# RobomasSwerve.net
KiCad netlist of a schematic drawn in EAGLE
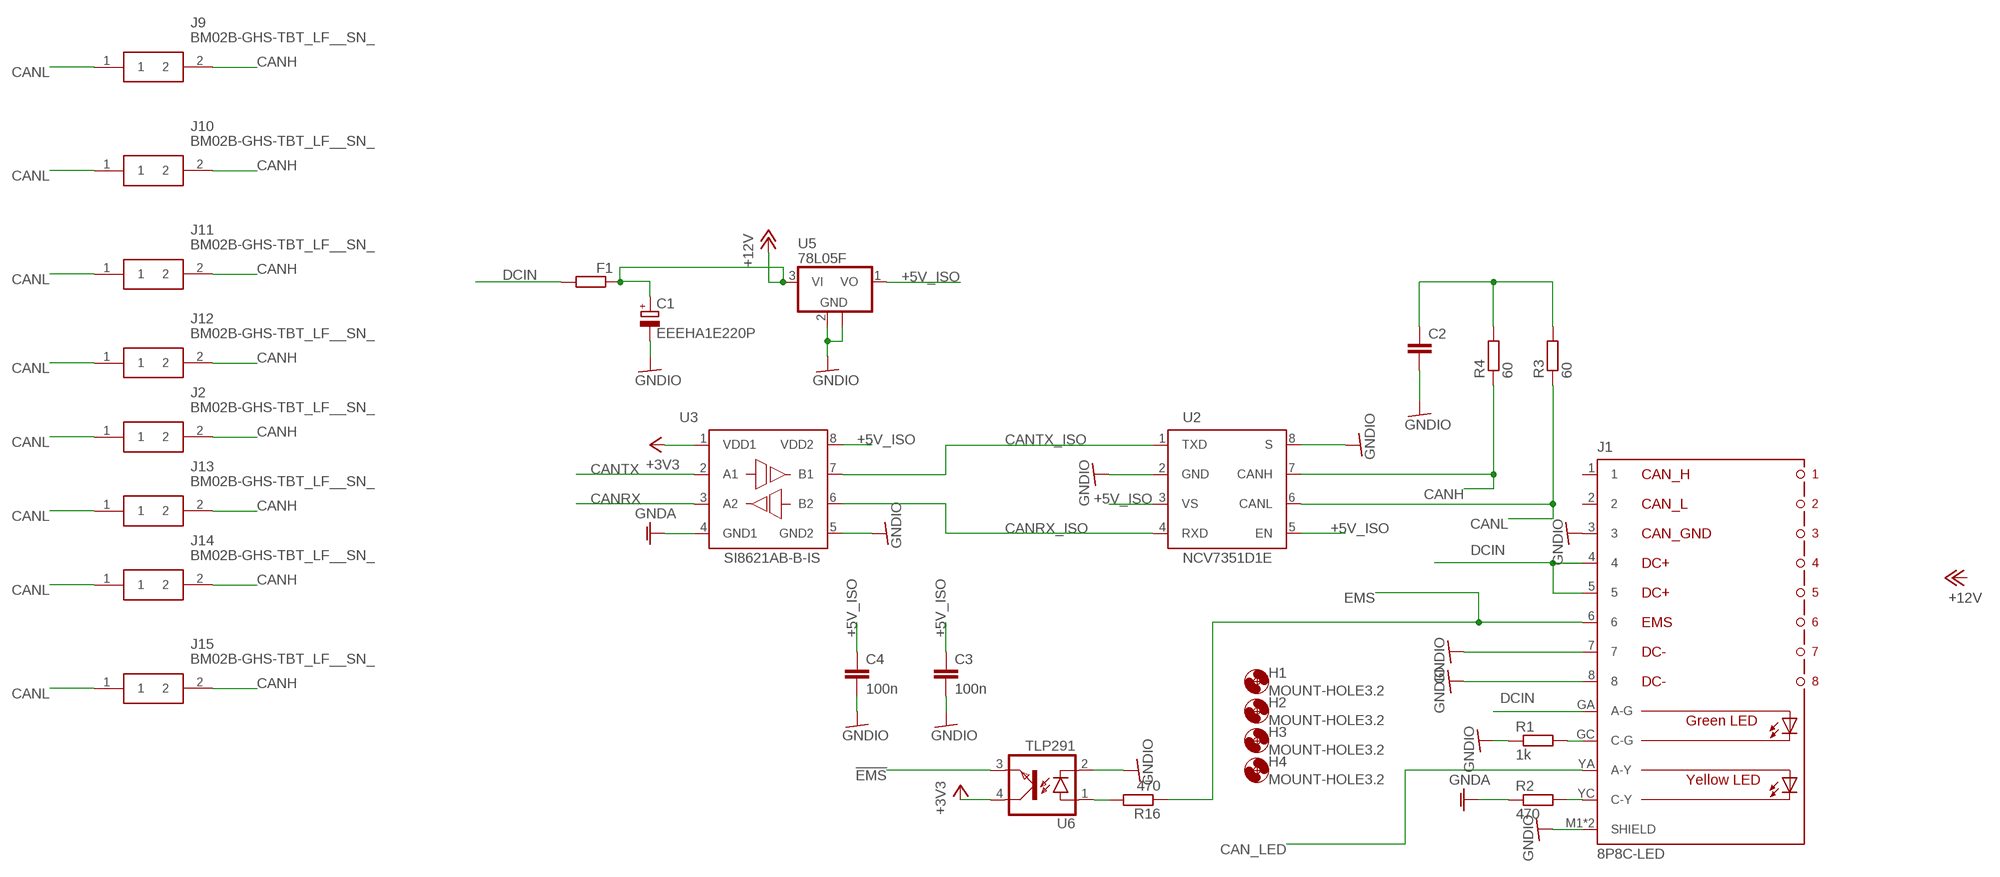
[diagram p0: schematic, sheet 1]
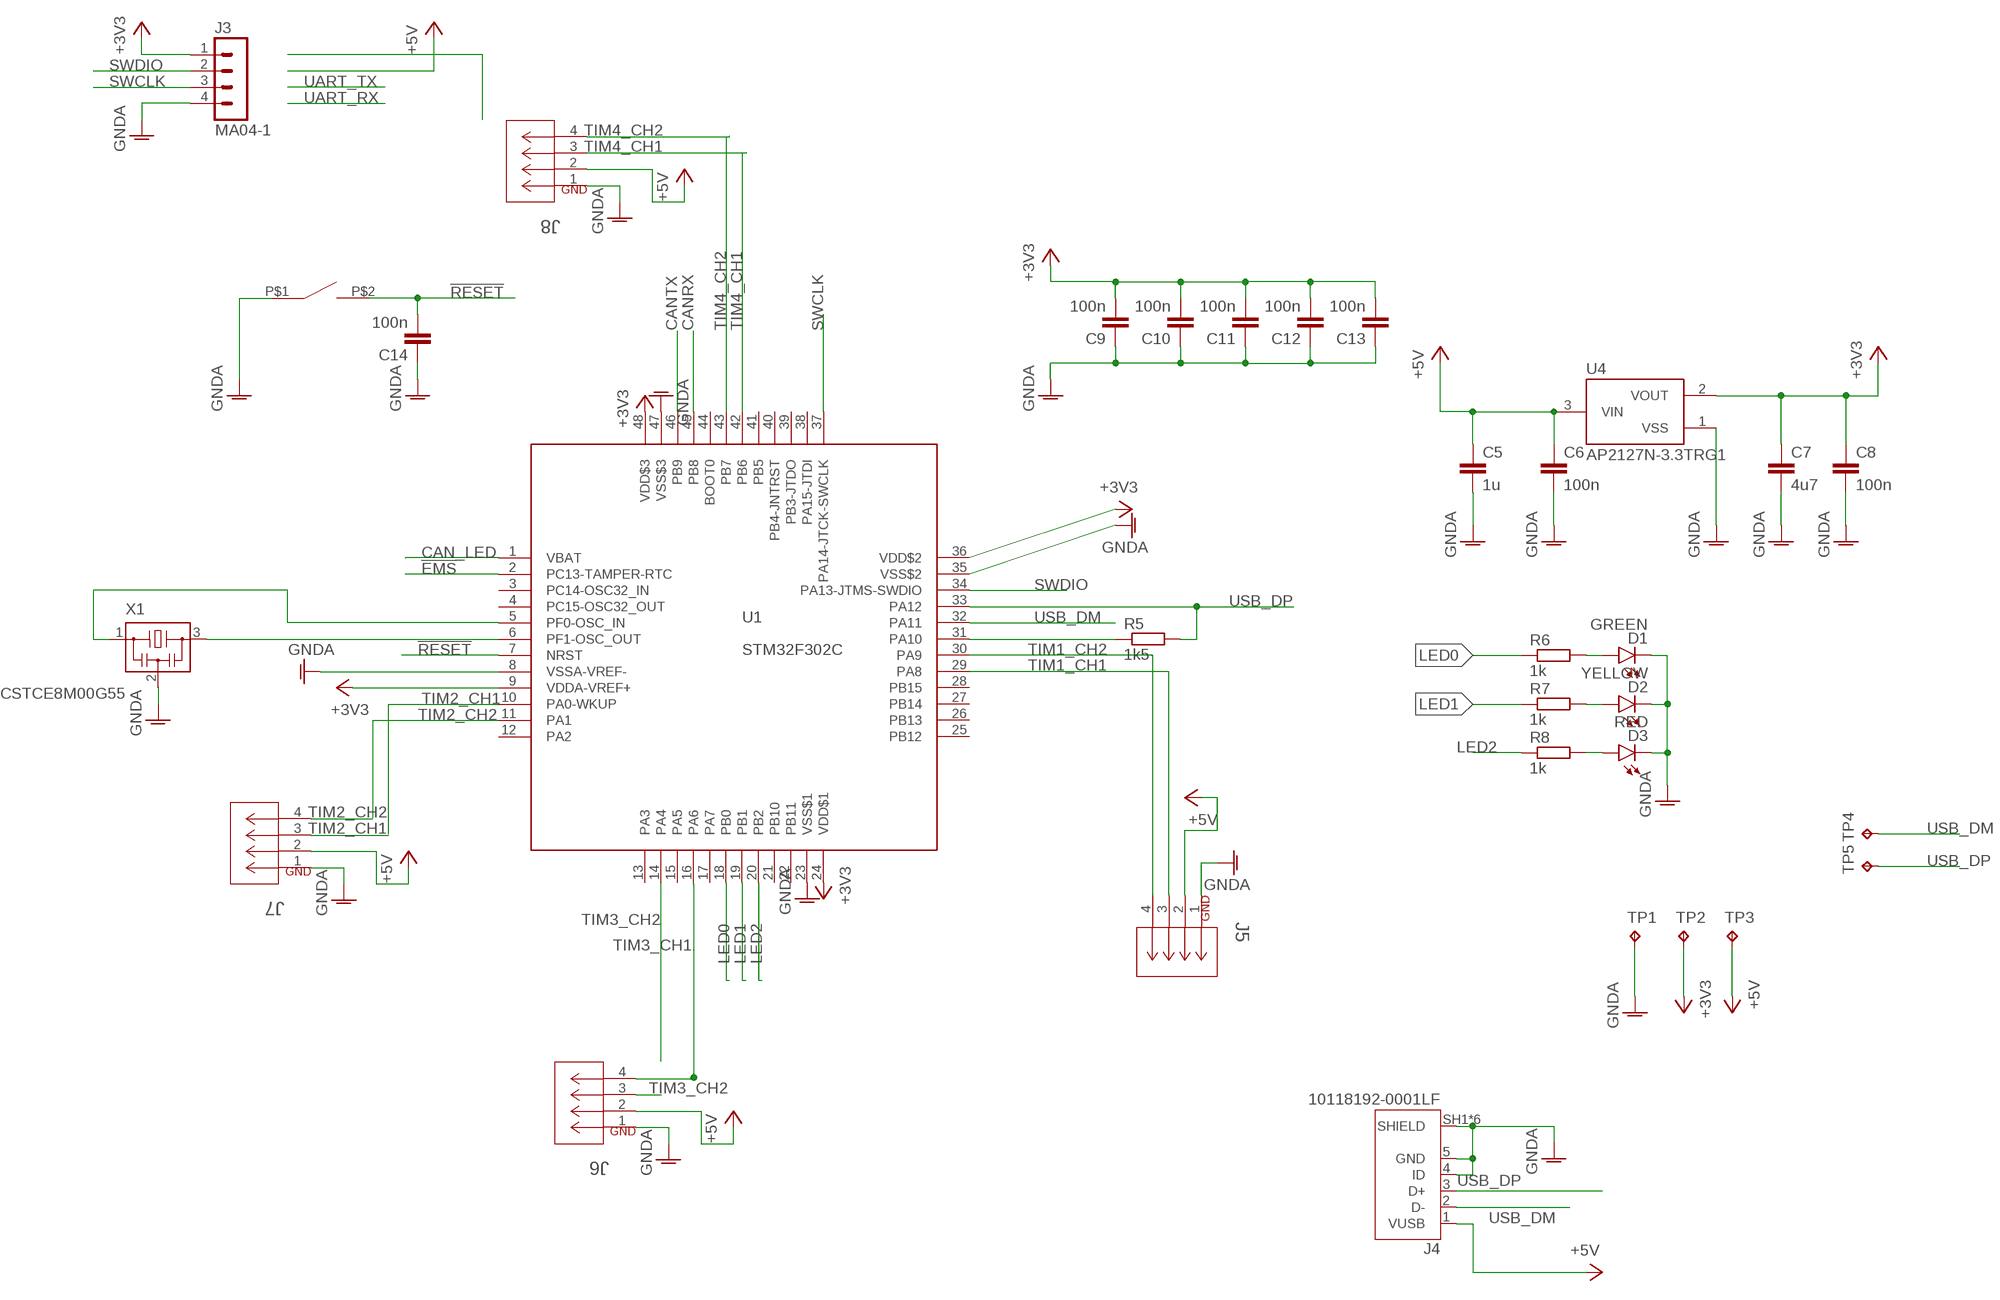
[diagram p1: schematic, sheet 2]

(export (version "E")
  (design (tool "Eeschema 10.0.6"))
  (components
    (comp (ref "C1")
      (value "EEEHA1E220P")
      (footprint "eagle-import:153CLV-0605")
      (libsource (lib "eagle-import") (part "CPOL-EU153CLV-0605"))
    )
    (comp (ref "C2")
      (value "C-EUC0603")
      (footprint "eagle-import:C0603")
      (libsource (lib "eagle-import") (part "rcl_334_C-EUC0603"))
    )
    (comp (ref "C3")
      (value "100n")
      (footprint "eagle-import:C0603")
      (libsource (lib "eagle-import") (part "rcl_334_C-EUC0603"))
    )
    (comp (ref "C4")
      (value "100n")
      (footprint "eagle-import:C0603")
      (libsource (lib "eagle-import") (part "rcl_334_C-EUC0603"))
    )
    (comp (ref "F1")
      (value "R-EU_R1206")
      (footprint "eagle-import:R1206")
      (libsource (lib "eagle-import") (part "rcl_334_R-EU_R1206"))
    )
    (comp (ref "H1")
      (value "MOUNT-HOLE3.2")
      (footprint "eagle-import:3,2")
      (libsource (lib "eagle-import") (part "MOUNT-HOLE3.2"))
    )
    (comp (ref "H2")
      (value "MOUNT-HOLE3.2")
      (footprint "eagle-import:3,2")
      (libsource (lib "eagle-import") (part "MOUNT-HOLE3.2"))
    )
    (comp (ref "H3")
      (value "MOUNT-HOLE3.2")
      (footprint "eagle-import:3,2")
      (libsource (lib "eagle-import") (part "MOUNT-HOLE3.2"))
    )
    (comp (ref "H4")
      (value "MOUNT-HOLE3.2")
      (footprint "eagle-import:3,2")
      (libsource (lib "eagle-import") (part "MOUNT-HOLE3.2"))
    )
    (comp (ref "J1")
      (value "8P8C-LED")
      (footprint "eagle-import:8P8C-LED")
      (libsource (lib "eagle-import") (part "8P8C-LED"))
    )
    (comp (ref "J2")
      (value "BM02B-GHS-TBT_LF__SN_")
      (footprint "eagle-import:BM02B-GHS-TBT_1")
      (fields (field (name "MANUFACTURER_PART_NUMBER") "BM02B-GHS-TBT(LF)(SN)"))
      (libsource (lib "eagle-import") (part "BM02B-GHS-TBT_LF__SN_"))
    )
    (comp (ref "J9")
      (value "BM02B-GHS-TBT_LF__SN_")
      (footprint "eagle-import:BM02B-GHS-TBT_1")
      (fields (field (name "MANUFACTURER_PART_NUMBER") "BM02B-GHS-TBT(LF)(SN)"))
      (libsource (lib "eagle-import") (part "BM02B-GHS-TBT_LF__SN_"))
    )
    (comp (ref "J10")
      (value "BM02B-GHS-TBT_LF__SN_")
      (footprint "eagle-import:BM02B-GHS-TBT_1")
      (fields (field (name "MANUFACTURER_PART_NUMBER") "BM02B-GHS-TBT(LF)(SN)"))
      (libsource (lib "eagle-import") (part "BM02B-GHS-TBT_LF__SN_"))
    )
    (comp (ref "J11")
      (value "BM02B-GHS-TBT_LF__SN_")
      (footprint "eagle-import:BM02B-GHS-TBT_1")
      (fields (field (name "MANUFACTURER_PART_NUMBER") "BM02B-GHS-TBT(LF)(SN)"))
      (libsource (lib "eagle-import") (part "BM02B-GHS-TBT_LF__SN_"))
    )
    (comp (ref "J12")
      (value "BM02B-GHS-TBT_LF__SN_")
      (footprint "eagle-import:BM02B-GHS-TBT_1")
      (fields (field (name "MANUFACTURER_PART_NUMBER") "BM02B-GHS-TBT(LF)(SN)"))
      (libsource (lib "eagle-import") (part "BM02B-GHS-TBT_LF__SN_"))
    )
    (comp (ref "J13")
      (value "BM02B-GHS-TBT_LF__SN_")
      (footprint "eagle-import:BM02B-GHS-TBT_1")
      (fields (field (name "MANUFACTURER_PART_NUMBER") "BM02B-GHS-TBT(LF)(SN)"))
      (libsource (lib "eagle-import") (part "BM02B-GHS-TBT_LF__SN_"))
    )
    (comp (ref "J14")
      (value "BM02B-GHS-TBT_LF__SN_")
      (footprint "eagle-import:BM02B-GHS-TBT_1")
      (fields (field (name "MANUFACTURER_PART_NUMBER") "BM02B-GHS-TBT(LF)(SN)"))
      (libsource (lib "eagle-import") (part "BM02B-GHS-TBT_LF__SN_"))
    )
    (comp (ref "J15")
      (value "BM02B-GHS-TBT_LF__SN_")
      (footprint "eagle-import:BM02B-GHS-TBT_1")
      (fields (field (name "MANUFACTURER_PART_NUMBER") "BM02B-GHS-TBT(LF)(SN)"))
      (libsource (lib "eagle-import") (part "BM02B-GHS-TBT_LF__SN_"))
    )
    (comp (ref "R1")
      (value "1k")
      (footprint "eagle-import:R0603")
      (libsource (lib "eagle-import") (part "rcl_334_R-EU_R0603"))
    )
    (comp (ref "R2")
      (value "470")
      (footprint "eagle-import:R0603")
      (libsource (lib "eagle-import") (part "rcl_334_R-EU_R0603"))
    )
    (comp (ref "R3")
      (value "60")
      (footprint "eagle-import:R0603")
      (libsource (lib "eagle-import") (part "rcl_334_R-EU_R0603"))
    )
    (comp (ref "R4")
      (value "60")
      (footprint "eagle-import:R0603")
      (libsource (lib "eagle-import") (part "rcl_334_R-EU_R0603"))
    )
    (comp (ref "R16")
      (value "470")
      (footprint "eagle-import:R0603")
      (libsource (lib "eagle-import") (part "rcl_334_R-EU_R0603"))
    )
    (comp (ref "U2")
      (value "NCV7351D1E")
      (footprint "eagle-import:SO08")
      (libsource (lib "eagle-import") (part "NCV7351D1E"))
    )
    (comp (ref "U3")
      (value "SI8621AB-B-IS")
      (footprint "eagle-import:SO08")
      (libsource (lib "eagle-import") (part "SI8621AB-B-IS"))
    )
    (comp (ref "U5")
      (value "78L05F")
      (footprint "eagle-import:SOT89")
      (libsource (lib "eagle-import") (part "78LF05"))
    )
    (comp (ref "U6")
      (value "TLP291")
      (footprint "eagle-import:MINI-FLAT-4")
      (libsource (lib "eagle-import") (part "TLP291"))
    )
    (comp (ref "C5")
      (value "1u")
      (footprint "eagle-import:C0603")
      (libsource (lib "eagle-import") (part "C-EUC0603"))
    )
    (comp (ref "C6")
      (value "100n")
      (footprint "eagle-import:C0603")
      (libsource (lib "eagle-import") (part "C-EUC0603"))
    )
    (comp (ref "C7")
      (value "4u7")
      (footprint "eagle-import:C0805")
      (libsource (lib "eagle-import") (part "C-EUC0805"))
    )
    (comp (ref "C8")
      (value "100n")
      (footprint "eagle-import:C0603")
      (libsource (lib "eagle-import") (part "C-EUC0603"))
    )
    (comp (ref "C9")
      (value "100n")
      (footprint "eagle-import:C0603")
      (libsource (lib "eagle-import") (part "C-EUC0603"))
    )
    (comp (ref "C10")
      (value "100n")
      (footprint "eagle-import:C0603")
      (libsource (lib "eagle-import") (part "C-EUC0603"))
    )
    (comp (ref "C11")
      (value "100n")
      (footprint "eagle-import:C0603")
      (libsource (lib "eagle-import") (part "C-EUC0603"))
    )
    (comp (ref "C12")
      (value "100n")
      (footprint "eagle-import:C0603")
      (libsource (lib "eagle-import") (part "C-EUC0603"))
    )
    (comp (ref "C13")
      (value "100n")
      (footprint "eagle-import:C0603")
      (libsource (lib "eagle-import") (part "C-EUC0603"))
    )
    (comp (ref "C14")
      (value "100n")
      (footprint "eagle-import:C0603")
      (libsource (lib "eagle-import") (part "C-EUC0603"))
    )
    (comp (ref "D1")
      (value "GREEN")
      (footprint "eagle-import:CHIPLED_0805")
      (libsource (lib "eagle-import") (part "LEDCHIPLED_0805"))
    )
    (comp (ref "D2")
      (value "YELLOW")
      (footprint "eagle-import:CHIPLED_0805")
      (libsource (lib "eagle-import") (part "LEDCHIPLED_0805"))
    )
    (comp (ref "D3")
      (value "RED")
      (footprint "eagle-import:CHIPLED_0805")
      (libsource (lib "eagle-import") (part "LEDCHIPLED_0805"))
    )
    (comp (ref "J3")
      (value "MA04-1")
      (footprint "eagle-import:MA04-1")
      (libsource (lib "eagle-import") (part "MA04-1"))
    )
    (comp (ref "J4")
      (value "10118192-0001LF")
      (footprint "eagle-import:AMPHENOL_10118192-0001LF")
      (fields (field (name "DIGI-KEY_PART_NUMBER") "609-4613-1-ND") (field (name "MF") "Amphenol ICC"))
      (libsource (lib "eagle-import") (part "10118192-0001LF"))
    )
    (comp (ref "J5")
      (value "EP2.5-4-SIDE")
      (footprint "eagle-import:CONN4_1744426-4")
      (fields (field (name "MANUFACTURER_PART_NUMBER") "17444264"))
      (libsource (lib "eagle-import") (part "EP2.5-4-SIDE"))
    )
    (comp (ref "J6")
      (value "EP2.5-4-SIDE")
      (footprint "eagle-import:CONN4_1744426-4")
      (fields (field (name "MANUFACTURER_PART_NUMBER") "17444264"))
      (libsource (lib "eagle-import") (part "EP2.5-4-SIDE"))
    )
    (comp (ref "J7")
      (value "EP2.5-4-SIDE")
      (footprint "eagle-import:CONN4_1744426-4")
      (fields (field (name "MANUFACTURER_PART_NUMBER") "17444264"))
      (libsource (lib "eagle-import") (part "EP2.5-4-SIDE"))
    )
    (comp (ref "J8")
      (value "EP2.5-4-SIDE")
      (footprint "eagle-import:CONN4_1744426-4")
      (fields (field (name "MANUFACTURER_PART_NUMBER") "17444264"))
      (libsource (lib "eagle-import") (part "EP2.5-4-SIDE"))
    )
    (comp (ref "R5")
      (value "1k5")
      (footprint "eagle-import:R0603")
      (libsource (lib "eagle-import") (part "R-EU_R0603"))
    )
    (comp (ref "R6")
      (value "1k")
      (footprint "eagle-import:R0603")
      (libsource (lib "eagle-import") (part "R-EU_R0603"))
    )
    (comp (ref "R7")
      (value "1k")
      (footprint "eagle-import:R0603")
      (libsource (lib "eagle-import") (part "R-EU_R0603"))
    )
    (comp (ref "R8")
      (value "1k")
      (footprint "eagle-import:R0603")
      (libsource (lib "eagle-import") (part "R-EU_R0603"))
    )
    (comp (ref "S1")
      (value "SWITCH_TACTILETOP")
      (footprint "eagle-import:SWITCH_TACTILE_3X6")
      (libsource (lib "eagle-import") (part "SWITCH_TACTILETOP"))
    )
    (comp (ref "TP1")
      (value "TPB1,27")
      (footprint "eagle-import:B1,27")
      (libsource (lib "eagle-import") (part "TPB1,27"))
    )
    (comp (ref "TP2")
      (value "TPB1,27")
      (footprint "eagle-import:B1,27")
      (libsource (lib "eagle-import") (part "TPB1,27"))
    )
    (comp (ref "TP3")
      (value "TPB1,27")
      (footprint "eagle-import:B1,27")
      (libsource (lib "eagle-import") (part "TPB1,27"))
    )
    (comp (ref "TP4")
      (value "TPB1,27")
      (footprint "eagle-import:B1,27")
      (libsource (lib "eagle-import") (part "TPB1,27"))
    )
    (comp (ref "TP5")
      (value "TPB1,27")
      (footprint "eagle-import:B1,27")
      (libsource (lib "eagle-import") (part "TPB1,27"))
    )
    (comp (ref "U1")
      (value "STM32F302C")
      (footprint "eagle-import:LQFP48")
      (libsource (lib "eagle-import") (part "STM32F303C"))
    )
    (comp (ref "U4")
      (value "AP2127N-3.3TRG1")
      (footprint "eagle-import:SOT95P240X110-3")
      (libsource (lib "eagle-import") (part "XC6206"))
    )
    (comp (ref "X1")
      (value "CSTCE8M00G55")
      (footprint "eagle-import:CSTCE8M00G55")
      (libsource (lib "eagle-import") (part "CSTCE8M00G55"))
    )
  )
  (nets
    (net (code "1") (name "+3V3") (class "Default")
      (node (ref "C10") (pin "2") (pinfunction "2_2") (pintype "passive"))
      (node (ref "C11") (pin "2") (pinfunction "2_2") (pintype "passive"))
      (node (ref "C12") (pin "2") (pinfunction "2_2") (pintype "passive"))
      (node (ref "C13") (pin "2") (pinfunction "2_2") (pintype "passive"))
      (node (ref "C7") (pin "1") (pinfunction "1_1") (pintype "passive"))
      (node (ref "C8") (pin "1") (pinfunction "1_1") (pintype "passive"))
      (node (ref "C9") (pin "2") (pinfunction "2_2") (pintype "passive"))
      (node (ref "J3") (pin "1") (pinfunction "1_1") (pintype "passive"))
      (node (ref "TP2") (pin "TP") (pinfunction "TP_TP") (pintype "input"))
      (node (ref "U1") (pin "24") (pinfunction "VDD$1_24") (pintype "passive"))
      (node (ref "U1") (pin "36") (pinfunction "VDD$2_36") (pintype "passive"))
      (node (ref "U1") (pin "48") (pinfunction "VDD$3_48") (pintype "passive"))
      (node (ref "U1") (pin "9") (pinfunction "VDDA-VREF+_9") (pintype "bidirectional"))
      (node (ref "U3") (pin "1") (pinfunction "VDD1_1") (pintype "power_in"))
      (node (ref "U4") (pin "2") (pinfunction "VOUT_2") (pintype "bidirectional"))
      (node (ref "U6") (pin "4") (pinfunction "COL_4") (pintype "passive"))
    )
    (net (code "2") (name "+5V") (class "Default")
      (node (ref "C5") (pin "1") (pinfunction "1_1") (pintype "passive"))
      (node (ref "C6") (pin "1") (pinfunction "1_1") (pintype "passive"))
      (node (ref "J4") (pin "1") (pinfunction "VUSB_1") (pintype "passive"))
      (node (ref "J5") (pin "2") (pinfunction "2_2") (pintype "passive"))
      (node (ref "J6") (pin "2") (pinfunction "2_2") (pintype "passive"))
      (node (ref "J7") (pin "2") (pinfunction "2_2") (pintype "passive"))
      (node (ref "J8") (pin "2") (pinfunction "2_2") (pintype "passive"))
      (node (ref "TP3") (pin "TP") (pinfunction "TP_TP") (pintype "input"))
      (node (ref "U4") (pin "3") (pinfunction "VIN_3") (pintype "bidirectional"))
    )
    (net (code "3") (name "+5V_ISO") (class "Default")
      (node (ref "C3") (pin "1") (pinfunction "1_1") (pintype "passive"))
      (node (ref "C4") (pin "1") (pinfunction "1_1") (pintype "passive"))
      (node (ref "U2") (pin "3") (pinfunction "VS_3") (pintype "power_in"))
      (node (ref "U2") (pin "5") (pinfunction "EN_5") (pintype "input"))
      (node (ref "U3") (pin "8") (pinfunction "VDD2_8") (pintype "power_in"))
      (node (ref "U5") (pin "1") (pinfunction "VO_1") (pintype "passive"))
    )
    (net (code "4") (name "+12V") (class "Default")
      (node (ref "C1") (pin "+") (pinfunction "+_+") (pintype "passive"))
      (node (ref "F1") (pin "1") (pinfunction "1_1") (pintype "passive"))
      (node (ref "U5") (pin "3") (pinfunction "VI_3") (pintype "input"))
    )
    (net (code "5") (name "CANH") (class "Default")
      (node (ref "J10") (pin "2") (pinfunction "2_2") (pintype "bidirectional"))
      (node (ref "J11") (pin "2") (pinfunction "2_2") (pintype "bidirectional"))
      (node (ref "J12") (pin "2") (pinfunction "2_2") (pintype "bidirectional"))
      (node (ref "J13") (pin "2") (pinfunction "2_2") (pintype "bidirectional"))
      (node (ref "J14") (pin "2") (pinfunction "2_2") (pintype "bidirectional"))
      (node (ref "J15") (pin "2") (pinfunction "2_2") (pintype "bidirectional"))
      (node (ref "J2") (pin "2") (pinfunction "2_2") (pintype "bidirectional"))
      (node (ref "J9") (pin "2") (pinfunction "2_2") (pintype "bidirectional"))
      (node (ref "R4") (pin "1") (pinfunction "1_1") (pintype "passive"))
      (node (ref "U2") (pin "7") (pinfunction "CANH_7") (pintype "output"))
    )
    (net (code "6") (name "CANL") (class "Default")
      (node (ref "J10") (pin "1") (pinfunction "1_1") (pintype "bidirectional"))
      (node (ref "J11") (pin "1") (pinfunction "1_1") (pintype "bidirectional"))
      (node (ref "J12") (pin "1") (pinfunction "1_1") (pintype "bidirectional"))
      (node (ref "J13") (pin "1") (pinfunction "1_1") (pintype "bidirectional"))
      (node (ref "J14") (pin "1") (pinfunction "1_1") (pintype "bidirectional"))
      (node (ref "J15") (pin "1") (pinfunction "1_1") (pintype "bidirectional"))
      (node (ref "J2") (pin "1") (pinfunction "1_1") (pintype "bidirectional"))
      (node (ref "J9") (pin "1") (pinfunction "1_1") (pintype "bidirectional"))
      (node (ref "R3") (pin "1") (pinfunction "1_1") (pintype "passive"))
      (node (ref "U2") (pin "6") (pinfunction "CANL_6") (pintype "output"))
    )
    (net (code "7") (name "CANRX") (class "Default")
      (node (ref "U1") (pin "45") (pinfunction "PB8_45") (pintype "bidirectional"))
      (node (ref "U3") (pin "3") (pinfunction "A2_3") (pintype "output"))
    )
    (net (code "8") (name "CANRX_ISO") (class "Default")
      (node (ref "U2") (pin "4") (pinfunction "RXD_4") (pintype "output"))
      (node (ref "U3") (pin "6") (pinfunction "B2_6") (pintype "output"))
    )
    (net (code "9") (name "CANTX") (class "Default")
      (node (ref "U1") (pin "46") (pinfunction "PB9_46") (pintype "bidirectional"))
      (node (ref "U3") (pin "2") (pinfunction "A1_2") (pintype "input"))
    )
    (net (code "10") (name "CANTX_ISO") (class "Default")
      (node (ref "U2") (pin "1") (pinfunction "TXD_1") (pintype "input"))
      (node (ref "U3") (pin "7") (pinfunction "B1_7") (pintype "output"))
    )
    (net (code "11") (name "CAN_LED") (class "Default")
      (node (ref "J1") (pin "YA") (pinfunction "A-Y_YA") (pintype "passive"))
      (node (ref "U1") (pin "1") (pinfunction "VBAT_1") (pintype "passive"))
    )
    (net (code "12") (name "DCIN") (class "Default")
      (node (ref "F1") (pin "2") (pinfunction "2_2") (pintype "passive"))
      (node (ref "J1") (pin "4") (pinfunction "4_4") (pintype "input"))
      (node (ref "J1") (pin "5") (pinfunction "5_5") (pintype "input"))
      (node (ref "J1") (pin "GA") (pinfunction "A-G_GA") (pintype "passive"))
    )
    (net (code "13") (name "EMS") (class "Default")
      (node (ref "J1") (pin "6") (pinfunction "6_6") (pintype "input"))
      (node (ref "R16") (pin "1") (pinfunction "1_1") (pintype "passive"))
    )
    (net (code "14") (name "GNDA") (class "Default")
      (node (ref "C10") (pin "1") (pinfunction "1_1") (pintype "passive"))
      (node (ref "C11") (pin "1") (pinfunction "1_1") (pintype "passive"))
      (node (ref "C12") (pin "1") (pinfunction "1_1") (pintype "passive"))
      (node (ref "C13") (pin "1") (pinfunction "1_1") (pintype "passive"))
      (node (ref "C14") (pin "1") (pinfunction "1_1") (pintype "passive"))
      (node (ref "C5") (pin "2") (pinfunction "2_2") (pintype "passive"))
      (node (ref "C6") (pin "2") (pinfunction "2_2") (pintype "passive"))
      (node (ref "C7") (pin "2") (pinfunction "2_2") (pintype "passive"))
      (node (ref "C8") (pin "2") (pinfunction "2_2") (pintype "passive"))
      (node (ref "C9") (pin "1") (pinfunction "1_1") (pintype "passive"))
      (node (ref "D1") (pin "C") (pinfunction "C_C") (pintype "passive"))
      (node (ref "D2") (pin "C") (pinfunction "C_C") (pintype "passive"))
      (node (ref "D3") (pin "C") (pinfunction "C_C") (pintype "passive"))
      (node (ref "J3") (pin "4") (pinfunction "4_4") (pintype "passive"))
      (node (ref "J4") (pin "4") (pinfunction "ID_4") (pintype "passive"))
      (node (ref "J4") (pin "5") (pinfunction "GND_5") (pintype "passive"))
      (node (ref "J4") (pin "SH1") (pinfunction "SHIELD_SH1") (pintype "passive"))
      (node (ref "J4") (pin "SH2") (pinfunction "SHIELD_SH2") (pintype "passive"))
      (node (ref "J4") (pin "SH3") (pinfunction "SHIELD_SH3") (pintype "passive"))
      (node (ref "J4") (pin "SH4") (pinfunction "SHIELD_SH4") (pintype "passive"))
      (node (ref "J4") (pin "SH5") (pinfunction "SHIELD_SH5") (pintype "passive"))
      (node (ref "J4") (pin "SH6") (pinfunction "SHIELD_SH6") (pintype "passive"))
      (node (ref "J5") (pin "1") (pinfunction "1_1") (pintype "passive"))
      (node (ref "J6") (pin "1") (pinfunction "1_1") (pintype "passive"))
      (node (ref "J7") (pin "1") (pinfunction "1_1") (pintype "passive"))
      (node (ref "J8") (pin "1") (pinfunction "1_1") (pintype "passive"))
      (node (ref "R2") (pin "1") (pinfunction "1_1") (pintype "passive"))
      (node (ref "S1") (pin "P$1") (pinfunction "1_P$1") (pintype "bidirectional"))
      (node (ref "TP1") (pin "TP") (pinfunction "TP_TP") (pintype "input"))
      (node (ref "U1") (pin "23") (pinfunction "VSS$1_23") (pintype "passive"))
      (node (ref "U1") (pin "35") (pinfunction "VSS$2_35") (pintype "passive"))
      (node (ref "U1") (pin "47") (pinfunction "VSS$3_47") (pintype "passive"))
      (node (ref "U1") (pin "8") (pinfunction "VSSA-VREF-_8") (pintype "bidirectional"))
      (node (ref "U3") (pin "4") (pinfunction "GND1_4") (pintype "power_in"))
      (node (ref "U4") (pin "1") (pinfunction "VSS_1") (pintype "bidirectional"))
      (node (ref "X1") (pin "2") (pinfunction "2_2") (pintype "passive"))
    )
    (net (code "15") (name "GNDIO") (class "Default")
      (node (ref "C1") (pin "-") (pinfunction "-_-") (pintype "passive"))
      (node (ref "C2") (pin "2") (pinfunction "2_2") (pintype "passive"))
      (node (ref "C3") (pin "2") (pinfunction "2_2") (pintype "passive"))
      (node (ref "C4") (pin "2") (pinfunction "2_2") (pintype "passive"))
      (node (ref "J1") (pin "3") (pinfunction "3_3") (pintype "input"))
      (node (ref "J1") (pin "7") (pinfunction "7_7") (pintype "input"))
      (node (ref "J1") (pin "8") (pinfunction "8_8") (pintype "input"))
      (node (ref "J1") (pin "M1") (pinfunction "SHIELD_M1") (pintype "passive"))
      (node (ref "J1") (pin "M2") (pinfunction "SHIELD_M2") (pintype "passive"))
      (node (ref "R1") (pin "1") (pinfunction "1_1") (pintype "passive"))
      (node (ref "U2") (pin "2") (pinfunction "GND_2") (pintype "power_in"))
      (node (ref "U2") (pin "8") (pinfunction "S_8") (pintype "input"))
      (node (ref "U3") (pin "5") (pinfunction "GND2_5") (pintype "power_in"))
      (node (ref "U5") (pin "2") (pinfunction "GND_2") (pintype "passive"))
      (node (ref "U5") (pin "2@1") (pinfunction "GND_2@1") (pintype "passive"))
      (node (ref "U6") (pin "2") (pinfunction "C_2") (pintype "passive"))
    )
    (net (code "16") (name "LED0") (class "Default")
      (node (ref "R6") (pin "1") (pinfunction "1_1") (pintype "passive"))
      (node (ref "U1") (pin "18") (pinfunction "PB0_18") (pintype "bidirectional"))
    )
    (net (code "17") (name "LED1") (class "Default")
      (node (ref "R7") (pin "1") (pinfunction "1_1") (pintype "passive"))
      (node (ref "U1") (pin "19") (pinfunction "PB1_19") (pintype "bidirectional"))
    )
    (net (code "18") (name "LED2") (class "Default")
      (node (ref "R8") (pin "1") (pinfunction "1_1") (pintype "passive"))
      (node (ref "U1") (pin "20") (pinfunction "PB2_20") (pintype "bidirectional"))
    )
    (net (code "19") (name "Net-(C2-Pad1)") (class "Default")
      (node (ref "C2") (pin "1") (pinfunction "1_1") (pintype "passive"))
      (node (ref "R3") (pin "2") (pinfunction "2_2") (pintype "passive"))
      (node (ref "R4") (pin "2") (pinfunction "2_2") (pintype "passive"))
    )
    (net (code "20") (name "Net-(D1-PadA)") (class "Default")
      (node (ref "D1") (pin "A") (pinfunction "A_A") (pintype "passive"))
      (node (ref "R6") (pin "2") (pinfunction "2_2") (pintype "passive"))
    )
    (net (code "21") (name "Net-(D2-PadA)") (class "Default")
      (node (ref "D2") (pin "A") (pinfunction "A_A") (pintype "passive"))
      (node (ref "R7") (pin "2") (pinfunction "2_2") (pintype "passive"))
    )
    (net (code "22") (name "Net-(D3-PadA)") (class "Default")
      (node (ref "D3") (pin "A") (pinfunction "A_A") (pintype "passive"))
      (node (ref "R8") (pin "2") (pinfunction "2_2") (pintype "passive"))
    )
    (net (code "23") (name "Net-(J1-C-G)") (class "Default")
      (node (ref "J1") (pin "GC") (pinfunction "C-G_GC") (pintype "passive"))
      (node (ref "R1") (pin "2") (pinfunction "2_2") (pintype "passive"))
    )
    (net (code "24") (name "Net-(J1-C-Y)") (class "Default")
      (node (ref "J1") (pin "YC") (pinfunction "C-Y_YC") (pintype "passive"))
      (node (ref "R2") (pin "2") (pinfunction "2_2") (pintype "passive"))
    )
    (net (code "25") (name "Net-(U1-PA10)") (class "Default")
      (node (ref "R5") (pin "1") (pinfunction "1_1") (pintype "passive"))
      (node (ref "U1") (pin "31") (pinfunction "PA10_31") (pintype "bidirectional"))
    )
    (net (code "26") (name "Net-(U1-PF0-OSC_IN)") (class "Default")
      (node (ref "U1") (pin "5") (pinfunction "PF0-OSC_IN_5") (pintype "input"))
      (node (ref "X1") (pin "1") (pinfunction "1_1") (pintype "passive"))
    )
    (net (code "27") (name "Net-(U1-PF1-OSC_OUT)") (class "Default")
      (node (ref "U1") (pin "6") (pinfunction "PF1-OSC_OUT_6") (pintype "output"))
      (node (ref "X1") (pin "3") (pinfunction "3_3") (pintype "passive"))
    )
    (net (code "28") (name "Net-(U6-A)") (class "Default")
      (node (ref "R16") (pin "2") (pinfunction "2_2") (pintype "passive"))
      (node (ref "U6") (pin "1") (pinfunction "A_1") (pintype "passive"))
    )
    (net (code "29") (name "SWCLK") (class "Default")
      (node (ref "J3") (pin "3") (pinfunction "3_3") (pintype "passive"))
      (node (ref "U1") (pin "37") (pinfunction "PA14-JTCK-SWCLK_37") (pintype "bidirectional"))
    )
    (net (code "30") (name "SWDIO") (class "Default")
      (node (ref "J3") (pin "2") (pinfunction "2_2") (pintype "passive"))
      (node (ref "U1") (pin "34") (pinfunction "PA13-JTMS-SWDIO_34") (pintype "bidirectional"))
    )
    (net (code "31") (name "TIM1_CH1") (class "Default")
      (node (ref "J5") (pin "3") (pinfunction "3_3") (pintype "passive"))
      (node (ref "U1") (pin "29") (pinfunction "PA8_29") (pintype "bidirectional"))
    )
    (net (code "32") (name "TIM1_CH2") (class "Default")
      (node (ref "J5") (pin "4") (pinfunction "4_4") (pintype "passive"))
      (node (ref "U1") (pin "30") (pinfunction "PA9_30") (pintype "bidirectional"))
    )
    (net (code "33") (name "TIM2_CH1") (class "Default")
      (node (ref "J7") (pin "3") (pinfunction "3_3") (pintype "passive"))
      (node (ref "U1") (pin "10") (pinfunction "PA0-WKUP_10") (pintype "bidirectional"))
    )
    (net (code "34") (name "TIM2_CH2") (class "Default")
      (node (ref "J7") (pin "4") (pinfunction "4_4") (pintype "passive"))
      (node (ref "U1") (pin "11") (pinfunction "PA1_11") (pintype "bidirectional"))
    )
    (net (code "35") (name "TIM3_CH1") (class "Default")
      (node (ref "J6") (pin "4") (pinfunction "4_4") (pintype "passive"))
      (node (ref "U1") (pin "16") (pinfunction "PA6_16") (pintype "bidirectional"))
    )
    (net (code "36") (name "TIM3_CH2") (class "Default")
      (node (ref "J6") (pin "3") (pinfunction "3_3") (pintype "passive"))
      (node (ref "U1") (pin "14") (pinfunction "PA4_14") (pintype "bidirectional"))
    )
    (net (code "37") (name "TIM4_CH1") (class "Default")
      (node (ref "J8") (pin "3") (pinfunction "3_3") (pintype "passive"))
      (node (ref "U1") (pin "42") (pinfunction "PB6_42") (pintype "bidirectional"))
    )
    (net (code "38") (name "TIM4_CH2") (class "Default")
      (node (ref "J8") (pin "4") (pinfunction "4_4") (pintype "passive"))
      (node (ref "U1") (pin "43") (pinfunction "PB7_43") (pintype "bidirectional"))
    )
    (net (code "41") (name "USB_DM") (class "Default")
      (node (ref "J4") (pin "2") (pinfunction "D-_2") (pintype "passive"))
      (node (ref "TP4") (pin "TP") (pinfunction "TP_TP") (pintype "input"))
      (node (ref "U1") (pin "32") (pinfunction "PA11_32") (pintype "bidirectional"))
    )
    (net (code "42") (name "USB_DP") (class "Default")
      (node (ref "J4") (pin "3") (pinfunction "D+_3") (pintype "passive"))
      (node (ref "R5") (pin "2") (pinfunction "2_2") (pintype "passive"))
      (node (ref "TP5") (pin "TP") (pinfunction "TP_TP") (pintype "input"))
      (node (ref "U1") (pin "33") (pinfunction "PA12_33") (pintype "bidirectional"))
    )
    (net (code "43") (name "unconnected-(J1-Pad1)") (class "Default")
      (node (ref "J1") (pin "1") (pinfunction "1_1") (pintype "input"))
    )
    (net (code "44") (name "unconnected-(J1-Pad2)") (class "Default")
      (node (ref "J1") (pin "2") (pinfunction "2_2") (pintype "input"))
    )
    (net (code "45") (name "unconnected-(U1-BOOT0-Pad44)") (class "Default")
      (node (ref "U1") (pin "44") (pinfunction "BOOT0_44") (pintype "input"))
    )
    (net (code "46") (name "unconnected-(U1-PA2-Pad12)") (class "Default")
      (node (ref "U1") (pin "12") (pinfunction "PA2_12") (pintype "bidirectional"))
    )
    (net (code "47") (name "unconnected-(U1-PA3-Pad13)") (class "Default")
      (node (ref "U1") (pin "13") (pinfunction "PA3_13") (pintype "bidirectional"))
    )
    (net (code "48") (name "unconnected-(U1-PA5-Pad15)") (class "Default")
      (node (ref "U1") (pin "15") (pinfunction "PA5_15") (pintype "bidirectional"))
    )
    (net (code "49") (name "unconnected-(U1-PA7-Pad17)") (class "Default")
      (node (ref "U1") (pin "17") (pinfunction "PA7_17") (pintype "bidirectional"))
    )
    (net (code "50") (name "unconnected-(U1-PA15-JTDI-Pad38)") (class "Default")
      (node (ref "U1") (pin "38") (pinfunction "PA15-JTDI_38") (pintype "bidirectional"))
    )
    (net (code "51") (name "unconnected-(U1-PB3-JTDO-Pad39)") (class "Default")
      (node (ref "U1") (pin "39") (pinfunction "PB3-JTDO_39") (pintype "bidirectional"))
    )
    (net (code "52") (name "unconnected-(U1-PB4-JNTRST-Pad40)") (class "Default")
      (node (ref "U1") (pin "40") (pinfunction "PB4-JNTRST_40") (pintype "bidirectional"))
    )
    (net (code "53") (name "unconnected-(U1-PB5-Pad41)") (class "Default")
      (node (ref "U1") (pin "41") (pinfunction "PB5_41") (pintype "bidirectional"))
    )
    (net (code "54") (name "unconnected-(U1-PB10-Pad21)") (class "Default")
      (node (ref "U1") (pin "21") (pinfunction "PB10_21") (pintype "bidirectional"))
    )
    (net (code "55") (name "unconnected-(U1-PB11-Pad22)") (class "Default")
      (node (ref "U1") (pin "22") (pinfunction "PB11_22") (pintype "bidirectional"))
    )
    (net (code "56") (name "unconnected-(U1-PB12-Pad25)") (class "Default")
      (node (ref "U1") (pin "25") (pinfunction "PB12_25") (pintype "bidirectional"))
    )
    (net (code "57") (name "unconnected-(U1-PB13-Pad26)") (class "Default")
      (node (ref "U1") (pin "26") (pinfunction "PB13_26") (pintype "bidirectional"))
    )
    (net (code "58") (name "unconnected-(U1-PB14-Pad27)") (class "Default")
      (node (ref "U1") (pin "27") (pinfunction "PB14_27") (pintype "bidirectional"))
    )
    (net (code "59") (name "unconnected-(U1-PB15-Pad28)") (class "Default")
      (node (ref "U1") (pin "28") (pinfunction "PB15_28") (pintype "bidirectional"))
    )
    (net (code "60") (name "unconnected-(U1-PC14-OSC32_IN-Pad3)") (class "Default")
      (node (ref "U1") (pin "3") (pinfunction "PC14-OSC32_IN_3") (pintype "bidirectional"))
    )
    (net (code "61") (name "unconnected-(U1-PC15-OSC32_OUT-Pad4)") (class "Default")
      (node (ref "U1") (pin "4") (pinfunction "PC15-OSC32_OUT_4") (pintype "bidirectional"))
    )
    (net (code "62") (name "~{EMS}") (class "Default")
      (node (ref "U1") (pin "2") (pinfunction "PC13-TAMPER-RTC_2") (pintype "bidirectional"))
      (node (ref "U6") (pin "3") (pinfunction "EMIT_3") (pintype "passive"))
    )
    (net (code "63") (name "~{RESET}") (class "Default")
      (node (ref "C14") (pin "2") (pinfunction "2_2") (pintype "passive"))
      (node (ref "S1") (pin "P$2") (pinfunction "2_P$2") (pintype "bidirectional"))
      (node (ref "U1") (pin "7") (pinfunction "NRST_7") (pintype "bidirectional"))
    )
  )
)
